# FIT_TCM_LEMO_OUT.net
KiCad netlist of a schematic drawn in Altium Designer
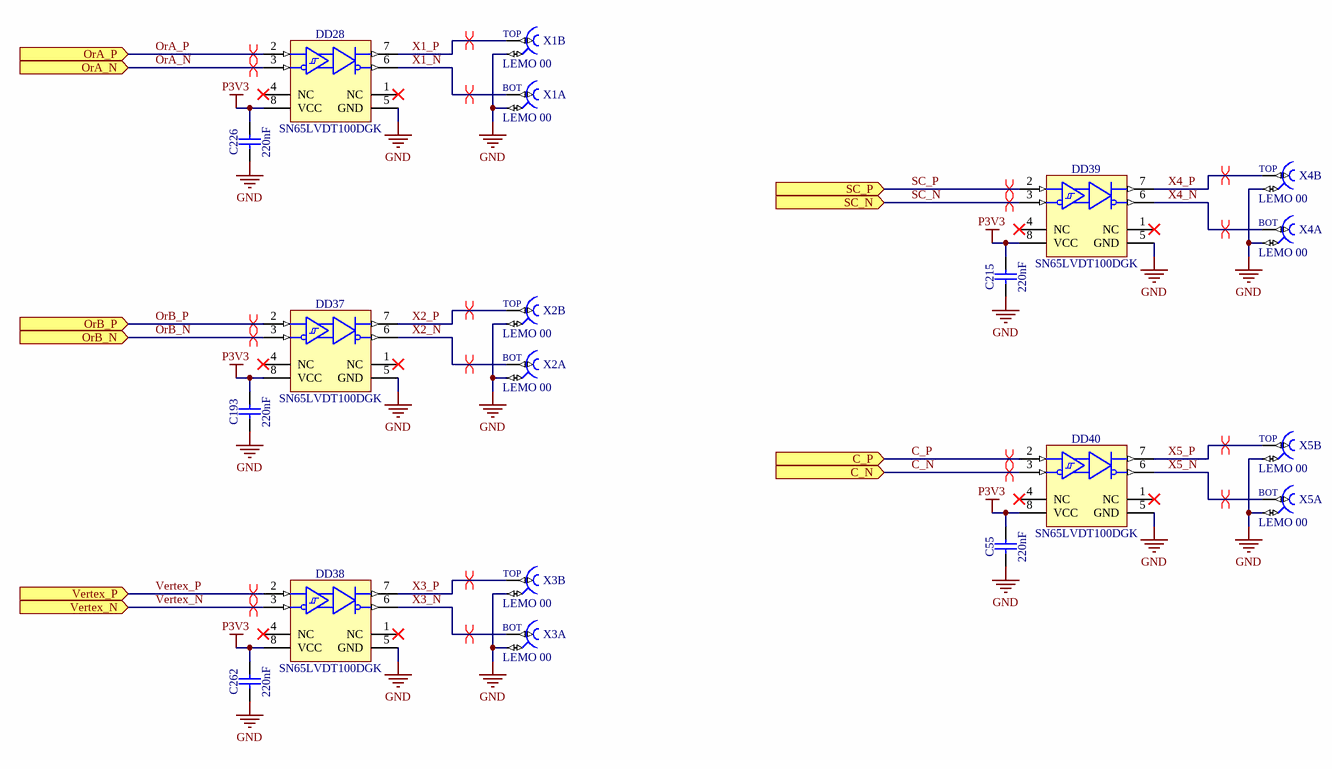
[diagram p0: FIT_TCM_LEMO_OUT.SchDoc]

(export (version "E")
  (design (tool "Eeschema 10.0.6"))
  (components
    (comp (ref "C55")
      (value "220nF")
      (footprint "CAPC2012X135N")
      (description "Non-polarised capacitor")
      (fields
        (field (name "PART NUMBER") "CC0805_220NF_50V_10%_X7R")
        (field (name "VOLTAGE") "50V")
        (field (name "AUTHOR") "CERN DEM JLC")
      )
      (libsource (lib "Capacitors") (part "Capacitor - non polarized"))
    )
    (comp (ref "C193")
      (value "220nF")
      (footprint "CAPC2012X135N")
      (description "Non-polarised capacitor")
      (fields
        (field (name "PART NUMBER") "CC0805_220NF_50V_10%_X7R")
        (field (name "VOLTAGE") "50V")
        (field (name "AUTHOR") "CERN DEM JLC")
      )
      (libsource (lib "Capacitors") (part "Capacitor - non polarized"))
    )
    (comp (ref "C215")
      (value "220nF")
      (footprint "CAPC2012X135N")
      (description "Non-polarised capacitor")
      (fields
        (field (name "PART NUMBER") "CC0805_220NF_50V_10%_X7R")
        (field (name "VOLTAGE") "50V")
        (field (name "AUTHOR") "CERN DEM JLC")
      )
      (libsource (lib "Capacitors") (part "Capacitor - non polarized"))
    )
    (comp (ref "C226")
      (value "220nF")
      (footprint "CAPC2012X135N")
      (description "Non-polarised capacitor")
      (fields
        (field (name "PART NUMBER") "CC0805_220NF_50V_10%_X7R")
        (field (name "VOLTAGE") "50V")
        (field (name "AUTHOR") "CERN DEM JLC")
      )
      (libsource (lib "Capacitors") (part "Capacitor - non polarized"))
    )
    (comp (ref "C262")
      (value "220nF")
      (footprint "CAPC2012X135N")
      (description "Non-polarised capacitor")
      (fields
        (field (name "PART NUMBER") "CC0805_220NF_50V_10%_X7R")
        (field (name "VOLTAGE") "50V")
        (field (name "AUTHOR") "CERN DEM JLC")
      )
      (libsource (lib "Capacitors") (part "Capacitor - non polarized"))
    )
    (comp (ref "DD28")
      (value "SN65LVDT100DGK")
      (footprint "SOP65P490X110-8N")
      (description "2Gbps LVDS/LVPECL/CML to LVDS Translator/Repeater")
      (fields (field (name "MANUFACTURER") "TEXAS INSTRUMENTS") (field (name "AUTHOR") "CERN DEM HF"))
      (libsource (lib "ICs And Semiconductors") (part "SN65LVDT100"))
    )
    (comp (ref "DD37")
      (value "SN65LVDT100DGK")
      (footprint "SOP65P490X110-8N")
      (description "2Gbps LVDS/LVPECL/CML to LVDS Translator/Repeater")
      (fields (field (name "MANUFACTURER") "TEXAS INSTRUMENTS") (field (name "AUTHOR") "CERN DEM HF"))
      (libsource (lib "ICs And Semiconductors") (part "SN65LVDT100"))
    )
    (comp (ref "DD38")
      (value "SN65LVDT100DGK")
      (footprint "SOP65P490X110-8N")
      (description "2Gbps LVDS/LVPECL/CML to LVDS Translator/Repeater")
      (fields (field (name "MANUFACTURER") "TEXAS INSTRUMENTS") (field (name "AUTHOR") "CERN DEM HF"))
      (libsource (lib "ICs And Semiconductors") (part "SN65LVDT100"))
    )
    (comp (ref "DD39")
      (value "SN65LVDT100DGK")
      (footprint "SOP65P490X110-8N")
      (description "2Gbps LVDS/LVPECL/CML to LVDS Translator/Repeater")
      (fields (field (name "MANUFACTURER") "TEXAS INSTRUMENTS") (field (name "AUTHOR") "CERN DEM HF"))
      (libsource (lib "ICs And Semiconductors") (part "SN65LVDT100"))
    )
    (comp (ref "DD40")
      (value "SN65LVDT100DGK")
      (footprint "SOP65P490X110-8N")
      (description "2Gbps LVDS/LVPECL/CML to LVDS Translator/Repeater")
      (fields (field (name "MANUFACTURER") "TEXAS INSTRUMENTS") (field (name "AUTHOR") "CERN DEM HF"))
      (libsource (lib "ICs And Semiconductors") (part "SN65LVDT100"))
    )
    (comp (ref "X1")
      (value "LEMO 00")
      (footprint "LEMO_EPY.00.250.NTN")
      (description "Dual Female Coax 1-2 Common Shield 3")
      (fields
        (field (name "PART NUMBER") "LEMO_EPY.00.250.NTN")
        (field (name "MANUFACTURER") "LEMO")
        (field (name "AUTHOR") "CERN DEM JMW")
      )
      (libsource (lib "Connectors") (part "LEMO_EPY.00.250.NTN"))
    )
    (comp (ref "X2")
      (value "LEMO 00")
      (footprint "LEMO_EPY.00.250.NTN")
      (description "Dual Female Coax 1-2 Common Shield 3")
      (fields
        (field (name "PART NUMBER") "LEMO_EPY.00.250.NTN")
        (field (name "MANUFACTURER") "LEMO")
        (field (name "AUTHOR") "CERN DEM JMW")
      )
      (libsource (lib "Connectors") (part "LEMO_EPY.00.250.NTN"))
    )
    (comp (ref "X3")
      (value "LEMO 00")
      (footprint "LEMO_EPY.00.250.NTN")
      (description "Dual Female Coax 1-2 Common Shield 3")
      (fields
        (field (name "PART NUMBER") "LEMO_EPY.00.250.NTN")
        (field (name "MANUFACTURER") "LEMO")
        (field (name "AUTHOR") "CERN DEM JMW")
      )
      (libsource (lib "Connectors") (part "LEMO_EPY.00.250.NTN"))
    )
    (comp (ref "X4")
      (value "LEMO 00")
      (footprint "LEMO_EPY.00.250.NTN")
      (description "Dual Female Coax 1-2 Common Shield 3")
      (fields
        (field (name "PART NUMBER") "LEMO_EPY.00.250.NTN")
        (field (name "MANUFACTURER") "LEMO")
        (field (name "AUTHOR") "CERN DEM JMW")
      )
      (libsource (lib "Connectors") (part "LEMO_EPY.00.250.NTN"))
    )
    (comp (ref "X5")
      (value "LEMO 00")
      (footprint "LEMO_EPY.00.250.NTN")
      (description "Dual Female Coax 1-2 Common Shield 3")
      (fields
        (field (name "PART NUMBER") "LEMO_EPY.00.250.NTN")
        (field (name "MANUFACTURER") "LEMO")
        (field (name "AUTHOR") "CERN DEM JMW")
      )
      (libsource (lib "Connectors") (part "LEMO_EPY.00.250.NTN"))
    )
  )
  (nets
    (net (code "1") (name "/C_N") (class "Default")
      (node (ref "DD40") (pin "3") (pinfunction "B_3") (pintype "input"))
    )
    (net (code "2") (name "/C_P") (class "Default")
      (node (ref "DD40") (pin "2") (pinfunction "A_2") (pintype "input"))
    )
    (net (code "3") (name "/OrA_N") (class "Default")
      (node (ref "DD28") (pin "3") (pinfunction "B_3") (pintype "input"))
    )
    (net (code "4") (name "/OrA_P") (class "Default")
      (node (ref "DD28") (pin "2") (pinfunction "A_2") (pintype "input"))
    )
    (net (code "5") (name "/OrB_N") (class "Default")
      (node (ref "DD37") (pin "3") (pinfunction "B_3") (pintype "input"))
    )
    (net (code "6") (name "/OrB_P") (class "Default")
      (node (ref "DD37") (pin "2") (pinfunction "A_2") (pintype "input"))
    )
    (net (code "7") (name "/SC_N") (class "Default")
      (node (ref "DD39") (pin "3") (pinfunction "B_3") (pintype "input"))
    )
    (net (code "8") (name "/SC_P") (class "Default")
      (node (ref "DD39") (pin "2") (pinfunction "A_2") (pintype "input"))
    )
    (net (code "9") (name "/Vertex_N") (class "Default")
      (node (ref "DD38") (pin "3") (pinfunction "B_3") (pintype "input"))
    )
    (net (code "10") (name "/Vertex_P") (class "Default")
      (node (ref "DD38") (pin "2") (pinfunction "A_2") (pintype "input"))
    )
    (net (code "11") (name "/X1_N") (class "Default")
      (node (ref "DD28") (pin "6") (pinfunction "Z_6") (pintype "output"))
      (node (ref "X1") (pin "1") (pinfunction "1_1") (pintype "bidirectional"))
    )
    (net (code "12") (name "/X1_P") (class "Default")
      (node (ref "DD28") (pin "7") (pinfunction "Y_7") (pintype "output"))
      (node (ref "X1") (pin "2") (pinfunction "2_2") (pintype "bidirectional"))
    )
    (net (code "13") (name "/X2_N") (class "Default")
      (node (ref "DD37") (pin "6") (pinfunction "Z_6") (pintype "output"))
      (node (ref "X2") (pin "1") (pinfunction "1_1") (pintype "bidirectional"))
    )
    (net (code "14") (name "/X2_P") (class "Default")
      (node (ref "DD37") (pin "7") (pinfunction "Y_7") (pintype "output"))
      (node (ref "X2") (pin "2") (pinfunction "2_2") (pintype "bidirectional"))
    )
    (net (code "15") (name "/X3_N") (class "Default")
      (node (ref "DD38") (pin "6") (pinfunction "Z_6") (pintype "output"))
      (node (ref "X3") (pin "1") (pinfunction "1_1") (pintype "bidirectional"))
    )
    (net (code "16") (name "/X3_P") (class "Default")
      (node (ref "DD38") (pin "7") (pinfunction "Y_7") (pintype "output"))
      (node (ref "X3") (pin "2") (pinfunction "2_2") (pintype "bidirectional"))
    )
    (net (code "17") (name "/X4_N") (class "Default")
      (node (ref "DD39") (pin "6") (pinfunction "Z_6") (pintype "output"))
      (node (ref "X4") (pin "1") (pinfunction "1_1") (pintype "bidirectional"))
    )
    (net (code "18") (name "/X4_P") (class "Default")
      (node (ref "DD39") (pin "7") (pinfunction "Y_7") (pintype "output"))
      (node (ref "X4") (pin "2") (pinfunction "2_2") (pintype "bidirectional"))
    )
    (net (code "19") (name "/X5_N") (class "Default")
      (node (ref "DD40") (pin "6") (pinfunction "Z_6") (pintype "output"))
      (node (ref "X5") (pin "1") (pinfunction "1_1") (pintype "bidirectional"))
    )
    (net (code "20") (name "/X5_P") (class "Default")
      (node (ref "DD40") (pin "7") (pinfunction "Y_7") (pintype "output"))
      (node (ref "X5") (pin "2") (pinfunction "2_2") (pintype "bidirectional"))
    )
    (net (code "21") (name "GND") (class "Default")
      (node (ref "C193") (pin "1") (pinfunction "1_1") (pintype "passive"))
      (node (ref "C215") (pin "1") (pinfunction "1_1") (pintype "passive"))
      (node (ref "C226") (pin "1") (pinfunction "1_1") (pintype "passive"))
      (node (ref "C262") (pin "1") (pinfunction "1_1") (pintype "passive"))
      (node (ref "C55") (pin "1") (pinfunction "1_1") (pintype "passive"))
      (node (ref "DD28") (pin "5") (pinfunction "GND_5") (pintype "power_in"))
      (node (ref "DD37") (pin "5") (pinfunction "GND_5") (pintype "power_in"))
      (node (ref "DD38") (pin "5") (pinfunction "GND_5") (pintype "power_in"))
      (node (ref "DD39") (pin "5") (pinfunction "GND_5") (pintype "power_in"))
      (node (ref "DD40") (pin "5") (pinfunction "GND_5") (pintype "power_in"))
      (node (ref "X1") (pin "3") (pinfunction "3_3") (pintype "bidirectional"))
      (node (ref "X2") (pin "3") (pinfunction "3_3") (pintype "bidirectional"))
      (node (ref "X3") (pin "3") (pinfunction "3_3") (pintype "bidirectional"))
      (node (ref "X4") (pin "3") (pinfunction "3_3") (pintype "bidirectional"))
      (node (ref "X5") (pin "3") (pinfunction "3_3") (pintype "bidirectional"))
    )
    (net (code "22") (name "P3V3") (class "Default")
      (node (ref "C193") (pin "2") (pinfunction "2_2") (pintype "passive"))
      (node (ref "C215") (pin "2") (pinfunction "2_2") (pintype "passive"))
      (node (ref "C226") (pin "2") (pinfunction "2_2") (pintype "passive"))
      (node (ref "C262") (pin "2") (pinfunction "2_2") (pintype "passive"))
      (node (ref "C55") (pin "2") (pinfunction "2_2") (pintype "passive"))
      (node (ref "DD28") (pin "8") (pinfunction "VCC_8") (pintype "power_in"))
      (node (ref "DD37") (pin "8") (pinfunction "VCC_8") (pintype "power_in"))
      (node (ref "DD38") (pin "8") (pinfunction "VCC_8") (pintype "power_in"))
      (node (ref "DD39") (pin "8") (pinfunction "VCC_8") (pintype "power_in"))
      (node (ref "DD40") (pin "8") (pinfunction "VCC_8") (pintype "power_in"))
    )
    (net (code "23") (name "unconnected-(DD28-NC-Pad1)") (class "Default")
      (node (ref "DD28") (pin "1") (pinfunction "NC_1") (pintype "passive+no_connect"))
    )
    (net (code "24") (name "unconnected-(DD28-NC-Pad4)") (class "Default")
      (node (ref "DD28") (pin "4") (pinfunction "NC_4") (pintype "passive+no_connect"))
    )
    (net (code "25") (name "unconnected-(DD37-NC-Pad1)") (class "Default")
      (node (ref "DD37") (pin "1") (pinfunction "NC_1") (pintype "passive+no_connect"))
    )
    (net (code "26") (name "unconnected-(DD37-NC-Pad4)") (class "Default")
      (node (ref "DD37") (pin "4") (pinfunction "NC_4") (pintype "passive+no_connect"))
    )
    (net (code "27") (name "unconnected-(DD38-NC-Pad1)") (class "Default")
      (node (ref "DD38") (pin "1") (pinfunction "NC_1") (pintype "passive+no_connect"))
    )
    (net (code "28") (name "unconnected-(DD38-NC-Pad4)") (class "Default")
      (node (ref "DD38") (pin "4") (pinfunction "NC_4") (pintype "passive+no_connect"))
    )
    (net (code "29") (name "unconnected-(DD39-NC-Pad1)") (class "Default")
      (node (ref "DD39") (pin "1") (pinfunction "NC_1") (pintype "passive+no_connect"))
    )
    (net (code "30") (name "unconnected-(DD39-NC-Pad4)") (class "Default")
      (node (ref "DD39") (pin "4") (pinfunction "NC_4") (pintype "passive+no_connect"))
    )
    (net (code "31") (name "unconnected-(DD40-NC-Pad1)") (class "Default")
      (node (ref "DD40") (pin "1") (pinfunction "NC_1") (pintype "passive+no_connect"))
    )
    (net (code "32") (name "unconnected-(DD40-NC-Pad4)") (class "Default")
      (node (ref "DD40") (pin "4") (pinfunction "NC_4") (pintype "passive+no_connect"))
    )
  )
)
